# G-PiC_Door_Controller.net
KiCad netlist of a schematic drawn in EAGLE
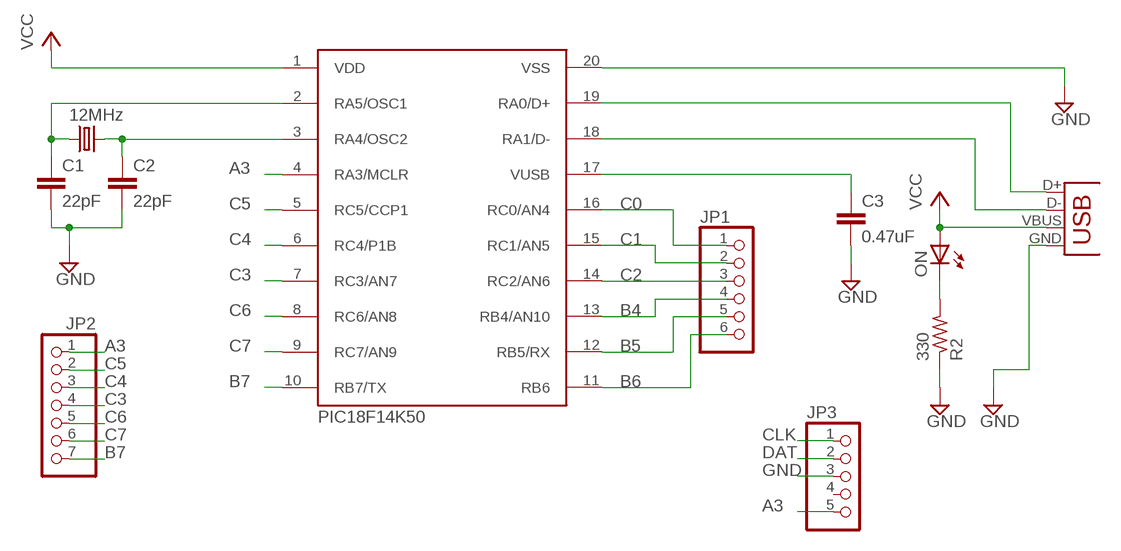
[diagram p0: schematic, sheet 1]

(export (version "E")
  (design (tool "Eeschema 10.0.6"))
  (components
    (comp (ref "C1")
      (value "22pF")
      (footprint "eagle-import:C5B3")
      (libsource (lib "eagle-import") (part "C5/3"))
    )
    (comp (ref "C2")
      (value "22pF")
      (footprint "eagle-import:C5B3")
      (libsource (lib "eagle-import") (part "C5/3"))
    )
    (comp (ref "C3")
      (value "0.47uF")
      (footprint "eagle-import:C5B3")
      (libsource (lib "eagle-import") (part "C5/3"))
    )
    (comp (ref "JP1")
      (value "PINHD-1X6")
      (footprint "eagle-import:1X06")
      (libsource (lib "eagle-import") (part "PINHD-1X6"))
    )
    (comp (ref "JP2")
      (value "PINHD-1X7")
      (footprint "eagle-import:1X07")
      (libsource (lib "eagle-import") (part "PINHD-1X7"))
    )
    (comp (ref "JP3")
      (value "PINHD-1X5")
      (footprint "eagle-import:1X05")
      (libsource (lib "eagle-import") (part "PINHD-1X5"))
    )
    (comp (ref "ON")
      (value "LED3MM")
      (footprint "eagle-import:LED3MM")
      (libsource (lib "eagle-import") (part "LED3MM"))
    )
    (comp (ref "PIC18F14K50")
      (value "PIC18F14K50")
      (footprint "eagle-import:DIL20")
      (libsource (lib "eagle-import") (part "PIC18F14K50"))
    )
    (comp (ref "R2")
      (value "330")
      (footprint "eagle-import:0204_7")
      (libsource (lib "eagle-import") (part "R-US_0204/7"))
    )
    (comp (ref "X3")
      (value "USBPTH")
      (footprint "eagle-import:USB-B-PTH")
      (libsource (lib "eagle-import") (part "USBPTH"))
    )
    (comp (ref "Y1")
      (value "12MHz")
      (footprint "eagle-import:HC49US")
      (libsource (lib "eagle-import") (part "CRYSTALHC49US"))
    )
  )
  (nets
    (net (code "1") (name "/A3") (class "Default")
      (node (ref "JP2") (pin "1") (pinfunction "1_1") (pintype "passive"))
      (node (ref "JP3") (pin "5") (pinfunction "5_5") (pintype "passive"))
      (node (ref "PIC18F14K50") (pin "4") (pinfunction "RA3/MCLR_4") (pintype "bidirectional"))
    )
    (net (code "2") (name "/B4") (class "Default")
      (node (ref "JP1") (pin "4") (pinfunction "4_4") (pintype "passive"))
      (node (ref "PIC18F14K50") (pin "13") (pinfunction "RB4/AN10_13") (pintype "bidirectional"))
    )
    (net (code "3") (name "/B5") (class "Default")
      (node (ref "JP1") (pin "5") (pinfunction "5_5") (pintype "passive"))
      (node (ref "PIC18F14K50") (pin "12") (pinfunction "RB5/RX_12") (pintype "bidirectional"))
    )
    (net (code "4") (name "/B6") (class "Default")
      (node (ref "JP1") (pin "6") (pinfunction "6_6") (pintype "passive"))
      (node (ref "PIC18F14K50") (pin "11") (pinfunction "RB6_11") (pintype "bidirectional"))
    )
    (net (code "5") (name "/B7") (class "Default")
      (node (ref "JP2") (pin "7") (pinfunction "7_7") (pintype "passive"))
      (node (ref "PIC18F14K50") (pin "10") (pinfunction "RB7/TX_10") (pintype "bidirectional"))
    )
    (net (code "6") (name "/C0") (class "Default")
      (node (ref "JP1") (pin "1") (pinfunction "1_1") (pintype "passive"))
      (node (ref "PIC18F14K50") (pin "16") (pinfunction "RC0/AN4_16") (pintype "bidirectional"))
    )
    (net (code "7") (name "/C1") (class "Default")
      (node (ref "JP1") (pin "2") (pinfunction "2_2") (pintype "passive"))
      (node (ref "PIC18F14K50") (pin "15") (pinfunction "RC1/AN5_15") (pintype "bidirectional"))
    )
    (net (code "8") (name "/C2") (class "Default")
      (node (ref "JP1") (pin "3") (pinfunction "3_3") (pintype "passive"))
      (node (ref "PIC18F14K50") (pin "14") (pinfunction "RC2/AN6_14") (pintype "bidirectional"))
    )
    (net (code "9") (name "/C3") (class "Default")
      (node (ref "JP2") (pin "4") (pinfunction "4_4") (pintype "passive"))
      (node (ref "PIC18F14K50") (pin "7") (pinfunction "RC3/AN7_7") (pintype "bidirectional"))
    )
    (net (code "10") (name "/C4") (class "Default")
      (node (ref "JP2") (pin "3") (pinfunction "3_3") (pintype "passive"))
      (node (ref "PIC18F14K50") (pin "6") (pinfunction "RC4/P1B_6") (pintype "bidirectional"))
    )
    (net (code "11") (name "/C5") (class "Default")
      (node (ref "JP2") (pin "2") (pinfunction "2_2") (pintype "passive"))
      (node (ref "PIC18F14K50") (pin "5") (pinfunction "RC5/CCP1_5") (pintype "bidirectional"))
    )
    (net (code "12") (name "/C6") (class "Default")
      (node (ref "JP2") (pin "5") (pinfunction "5_5") (pintype "passive"))
      (node (ref "PIC18F14K50") (pin "8") (pinfunction "RC6/AN8_8") (pintype "bidirectional"))
    )
    (net (code "13") (name "/C7") (class "Default")
      (node (ref "JP2") (pin "6") (pinfunction "6_6") (pintype "passive"))
      (node (ref "PIC18F14K50") (pin "9") (pinfunction "RC7/AN9_9") (pintype "bidirectional"))
    )
    (net (code "14") (name "/CLK") (class "Default")
      (node (ref "JP3") (pin "1") (pinfunction "1_1") (pintype "passive"))
      (node (ref "PIC18F14K50") (pin "18") (pinfunction "RA1/D-_18") (pintype "bidirectional"))
      (node (ref "X3") (pin "D-") (pinfunction "D-_D-") (pintype "bidirectional"))
    )
    (net (code "15") (name "/DAT") (class "Default")
      (node (ref "JP3") (pin "2") (pinfunction "2_2") (pintype "passive"))
      (node (ref "PIC18F14K50") (pin "19") (pinfunction "RA0/D+_19") (pintype "bidirectional"))
      (node (ref "X3") (pin "D+") (pinfunction "D+_D+") (pintype "bidirectional"))
    )
    (net (code "16") (name "GND") (class "Default")
      (node (ref "C1") (pin "2") (pinfunction "2_2") (pintype "passive"))
      (node (ref "C2") (pin "2") (pinfunction "2_2") (pintype "passive"))
      (node (ref "C3") (pin "2") (pinfunction "2_2") (pintype "passive"))
      (node (ref "JP3") (pin "3") (pinfunction "3_3") (pintype "passive"))
      (node (ref "PIC18F14K50") (pin "20") (pinfunction "VSS_20") (pintype "bidirectional"))
      (node (ref "R2") (pin "1") (pinfunction "1_1") (pintype "passive"))
      (node (ref "X3") (pin "GND") (pinfunction "GND_GND") (pintype "bidirectional"))
    )
    (net (code "17") (name "Net-(ON-C)") (class "Default")
      (node (ref "ON") (pin "K") (pinfunction "C_K") (pintype "passive"))
      (node (ref "R2") (pin "2") (pinfunction "2_2") (pintype "passive"))
    )
    (net (code "18") (name "Net-(PIC18F14K50-RA4{slash}OSC2)") (class "Default")
      (node (ref "C2") (pin "1") (pinfunction "1_1") (pintype "passive"))
      (node (ref "PIC18F14K50") (pin "3") (pinfunction "RA4/OSC2_3") (pintype "bidirectional"))
      (node (ref "Y1") (pin "2") (pinfunction "2_2") (pintype "passive"))
    )
    (net (code "19") (name "Net-(PIC18F14K50-RA5{slash}OSC1)") (class "Default")
      (node (ref "C1") (pin "1") (pinfunction "1_1") (pintype "passive"))
      (node (ref "PIC18F14K50") (pin "2") (pinfunction "RA5/OSC1_2") (pintype "bidirectional"))
      (node (ref "Y1") (pin "1") (pinfunction "1_1") (pintype "passive"))
    )
    (net (code "20") (name "Net-(PIC18F14K50-VUSB)") (class "Default")
      (node (ref "C3") (pin "1") (pinfunction "1_1") (pintype "passive"))
      (node (ref "PIC18F14K50") (pin "17") (pinfunction "VUSB_17") (pintype "bidirectional"))
    )
    (net (code "21") (name "VCC") (class "Default")
      (node (ref "ON") (pin "A") (pinfunction "A_A") (pintype "passive"))
      (node (ref "PIC18F14K50") (pin "1") (pinfunction "VDD_1") (pintype "bidirectional"))
      (node (ref "X3") (pin "VBUS") (pinfunction "VBUS_VBUS") (pintype "bidirectional"))
    )
    (net (code "22") (name "unconnected-(JP3-Pad4)") (class "Default")
      (node (ref "JP3") (pin "4") (pinfunction "4_4") (pintype "passive"))
    )
  )
)
